# imsensor-v01.net
KiCad netlist of a schematic drawn in EAGLE
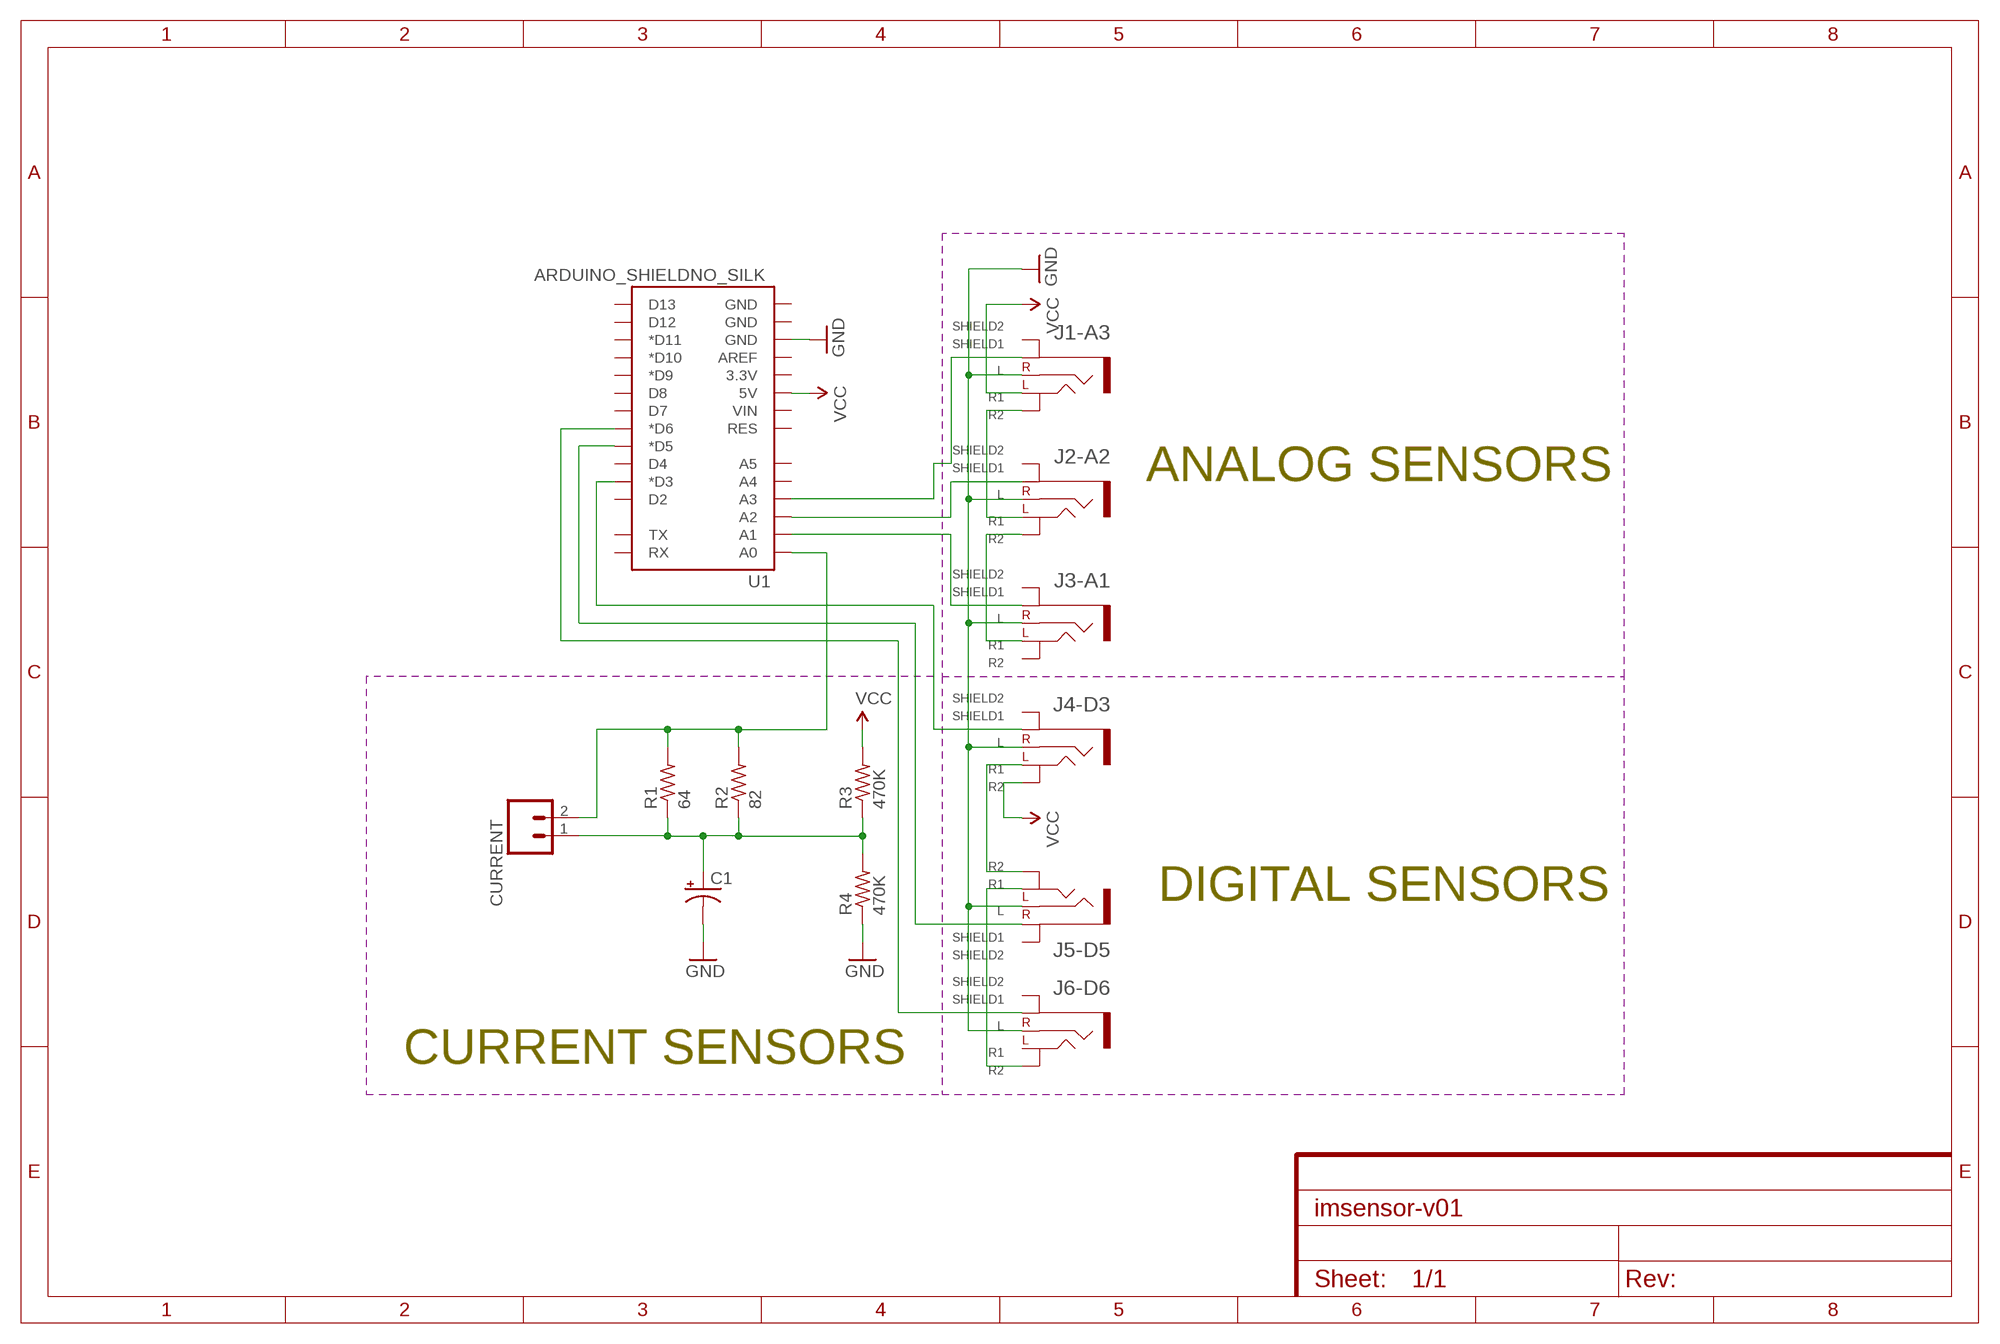
[diagram p0: schematic, sheet 1]

(export (version "E")
  (design (tool "Eeschema 10.0.6"))
  (components
    (comp (ref "C1")
      (value "10UF-25V-20%(PTH)")
      (footprint "eagle-import:CPOL-RADIAL-10UF-25V")
      (libsource (lib "eagle-import") (part "10UF-25V-20%(PTH)"))
    )
    (comp (ref "CURRENT")
      (value "M02PTH")
      (footprint "eagle-import:1X02")
      (libsource (lib "eagle-import") (part "M02PTH"))
    )
    (comp (ref "J1-A3")
      (value "PJ-313-SPAD")
      (footprint "eagle-import:PJ-313-5PIN-SMALL")
      (libsource (lib "eagle-import") (part "PJ-313-SPAD"))
    )
    (comp (ref "J2-A2")
      (value "PJ-313-SPAD")
      (footprint "eagle-import:PJ-313-5PIN-SMALL")
      (libsource (lib "eagle-import") (part "PJ-313-SPAD"))
    )
    (comp (ref "J3-A1")
      (value "PJ-313-SPAD")
      (footprint "eagle-import:PJ-313-5PIN-SMALL")
      (libsource (lib "eagle-import") (part "PJ-313-SPAD"))
    )
    (comp (ref "J4-D3")
      (value "PJ-313-SPAD")
      (footprint "eagle-import:PJ-313-5PIN-SMALL")
      (libsource (lib "eagle-import") (part "PJ-313-SPAD"))
    )
    (comp (ref "J5-D5")
      (value "PJ-313-SPAD")
      (footprint "eagle-import:PJ-313-5PIN-SMALL")
      (libsource (lib "eagle-import") (part "PJ-313-SPAD"))
    )
    (comp (ref "J6-D6")
      (value "PJ-313-SPAD")
      (footprint "eagle-import:PJ-313-5PIN-SMALL")
      (libsource (lib "eagle-import") (part "PJ-313-SPAD"))
    )
    (comp (ref "R1")
      (value "64")
      (footprint "eagle-import:0207_10")
      (libsource (lib "eagle-import") (part "R-US_0207/10"))
    )
    (comp (ref "R2")
      (value "82")
      (footprint "eagle-import:0207_10")
      (libsource (lib "eagle-import") (part "R-US_0207/10"))
    )
    (comp (ref "R3")
      (value "470K")
      (footprint "eagle-import:0207_10")
      (libsource (lib "eagle-import") (part "R-US_0207/10"))
    )
    (comp (ref "R4")
      (value "470K")
      (footprint "eagle-import:0207_10")
      (libsource (lib "eagle-import") (part "R-US_0207/10"))
    )
    (comp (ref "U1")
      (value "ARDUINO_SHIELDNO_SILK")
      (footprint "eagle-import:DUEMILANOVE_VIAS")
      (libsource (lib "eagle-import") (part "ARDUINO_SHIELDNO_SILK"))
    )
  )
  (nets
    (net (code "1") (name "GND") (class "Default")
      (node (ref "C1") (pin "2") (pinfunction "-_2") (pintype "passive"))
      (node (ref "J1-A3") (pin "2") (pinfunction "R_2") (pintype "bidirectional"))
      (node (ref "J2-A2") (pin "2") (pinfunction "R_2") (pintype "bidirectional"))
      (node (ref "J3-A1") (pin "2") (pinfunction "R_2") (pintype "bidirectional"))
      (node (ref "J4-D3") (pin "2") (pinfunction "R_2") (pintype "bidirectional"))
      (node (ref "J5-D5") (pin "2") (pinfunction "R_2") (pintype "bidirectional"))
      (node (ref "J6-D6") (pin "2") (pinfunction "R_2") (pintype "bidirectional"))
      (node (ref "R4") (pin "1") (pinfunction "1_1") (pintype "passive"))
      (node (ref "U1") (pin "GND@2") (pinfunction "GND_GND@2") (pintype "bidirectional"))
    )
    (net (code "2") (name "Net-(C1-+)") (class "Default")
      (node (ref "C1") (pin "1") (pinfunction "+_1") (pintype "passive"))
      (node (ref "CURRENT") (pin "1") (pinfunction "1_1") (pintype "passive"))
      (node (ref "R1") (pin "1") (pinfunction "1_1") (pintype "passive"))
      (node (ref "R2") (pin "1") (pinfunction "1_1") (pintype "passive"))
      (node (ref "R3") (pin "1") (pinfunction "1_1") (pintype "passive"))
      (node (ref "R4") (pin "2") (pinfunction "2_2") (pintype "passive"))
    )
    (net (code "3") (name "Net-(CURRENT-Pad2)") (class "Default")
      (node (ref "CURRENT") (pin "2") (pinfunction "2_2") (pintype "passive"))
      (node (ref "R1") (pin "2") (pinfunction "2_2") (pintype "passive"))
      (node (ref "R2") (pin "2") (pinfunction "2_2") (pintype "passive"))
      (node (ref "U1") (pin "A0") (pinfunction "A0_A0") (pintype "bidirectional"))
    )
    (net (code "4") (name "Net-(J1-A3-L2)") (class "Default")
      (node (ref "J1-A3") (pin "3.2") (pinfunction "L2_3.2") (pintype "bidirectional"))
      (node (ref "J2-A2") (pin "3.1") (pinfunction "L1_3.1") (pintype "bidirectional"))
    )
    (net (code "5") (name "Net-(J1-A3-SHIELD1)") (class "Default")
      (node (ref "J1-A3") (pin "1.1") (pinfunction "SHIELD1_1.1") (pintype "bidirectional"))
      (node (ref "U1") (pin "A3") (pinfunction "A3_A3") (pintype "bidirectional"))
    )
    (net (code "6") (name "Net-(J2-A2-L2)") (class "Default")
      (node (ref "J2-A2") (pin "3.2") (pinfunction "L2_3.2") (pintype "bidirectional"))
      (node (ref "J3-A1") (pin "3.1") (pinfunction "L1_3.1") (pintype "bidirectional"))
    )
    (net (code "7") (name "Net-(J2-A2-SHIELD1)") (class "Default")
      (node (ref "J2-A2") (pin "1.1") (pinfunction "SHIELD1_1.1") (pintype "bidirectional"))
      (node (ref "U1") (pin "A2") (pinfunction "A2_A2") (pintype "bidirectional"))
    )
    (net (code "8") (name "Net-(J3-A1-SHIELD1)") (class "Default")
      (node (ref "J3-A1") (pin "1.1") (pinfunction "SHIELD1_1.1") (pintype "bidirectional"))
      (node (ref "U1") (pin "A1") (pinfunction "A1_A1") (pintype "bidirectional"))
    )
    (net (code "9") (name "Net-(J4-D3-L1)") (class "Default")
      (node (ref "J4-D3") (pin "3.1") (pinfunction "L1_3.1") (pintype "bidirectional"))
      (node (ref "J5-D5") (pin "3.2") (pinfunction "L2_3.2") (pintype "bidirectional"))
    )
    (net (code "10") (name "Net-(J4-D3-SHIELD1)") (class "Default")
      (node (ref "J4-D3") (pin "1.1") (pinfunction "SHIELD1_1.1") (pintype "bidirectional"))
      (node (ref "U1") (pin "D3") (pinfunction "*D3_D3") (pintype "bidirectional"))
    )
    (net (code "11") (name "Net-(J5-D5-L1)") (class "Default")
      (node (ref "J5-D5") (pin "3.1") (pinfunction "L1_3.1") (pintype "bidirectional"))
      (node (ref "J6-D6") (pin "3.2") (pinfunction "L2_3.2") (pintype "bidirectional"))
    )
    (net (code "12") (name "Net-(J5-D5-SHIELD1)") (class "Default")
      (node (ref "J5-D5") (pin "1.1") (pinfunction "SHIELD1_1.1") (pintype "bidirectional"))
      (node (ref "U1") (pin "D5") (pinfunction "*D5_D5") (pintype "bidirectional"))
    )
    (net (code "13") (name "Net-(J6-D6-SHIELD1)") (class "Default")
      (node (ref "J6-D6") (pin "1.1") (pinfunction "SHIELD1_1.1") (pintype "bidirectional"))
      (node (ref "U1") (pin "D6") (pinfunction "*D6_D6") (pintype "bidirectional"))
    )
    (net (code "14") (name "VCC") (class "Default")
      (node (ref "J1-A3") (pin "3.1") (pinfunction "L1_3.1") (pintype "bidirectional"))
      (node (ref "J4-D3") (pin "3.2") (pinfunction "L2_3.2") (pintype "bidirectional"))
      (node (ref "R3") (pin "2") (pinfunction "2_2") (pintype "passive"))
      (node (ref "U1") (pin "5V") (pinfunction "5V_5V") (pintype "bidirectional"))
    )
    (net (code "15") (name "unconnected-(J1-A3-SHIELD2-Pad1.2)") (class "Default")
      (node (ref "J1-A3") (pin "1.2") (pinfunction "SHIELD2_1.2") (pintype "bidirectional"))
    )
    (net (code "16") (name "unconnected-(J2-A2-SHIELD2-Pad1.2)") (class "Default")
      (node (ref "J2-A2") (pin "1.2") (pinfunction "SHIELD2_1.2") (pintype "bidirectional"))
    )
    (net (code "17") (name "unconnected-(J3-A1-L2-Pad3.2)") (class "Default")
      (node (ref "J3-A1") (pin "3.2") (pinfunction "L2_3.2") (pintype "bidirectional"))
    )
    (net (code "18") (name "unconnected-(J3-A1-SHIELD2-Pad1.2)") (class "Default")
      (node (ref "J3-A1") (pin "1.2") (pinfunction "SHIELD2_1.2") (pintype "bidirectional"))
    )
    (net (code "19") (name "unconnected-(J4-D3-SHIELD2-Pad1.2)") (class "Default")
      (node (ref "J4-D3") (pin "1.2") (pinfunction "SHIELD2_1.2") (pintype "bidirectional"))
    )
    (net (code "20") (name "unconnected-(J5-D5-SHIELD2-Pad1.2)") (class "Default")
      (node (ref "J5-D5") (pin "1.2") (pinfunction "SHIELD2_1.2") (pintype "bidirectional"))
    )
    (net (code "21") (name "unconnected-(J6-D6-L1-Pad3.1)") (class "Default")
      (node (ref "J6-D6") (pin "3.1") (pinfunction "L1_3.1") (pintype "bidirectional"))
    )
    (net (code "22") (name "unconnected-(J6-D6-SHIELD2-Pad1.2)") (class "Default")
      (node (ref "J6-D6") (pin "1.2") (pinfunction "SHIELD2_1.2") (pintype "bidirectional"))
    )
    (net (code "23") (name "unconnected-(U1-*D9-PadD9)") (class "Default")
      (node (ref "U1") (pin "D9") (pinfunction "*D9_D9") (pintype "bidirectional"))
    )
    (net (code "24") (name "unconnected-(U1-*D10-PadD10)") (class "Default")
      (node (ref "U1") (pin "D10") (pinfunction "*D10_D10") (pintype "bidirectional"))
    )
    (net (code "25") (name "unconnected-(U1-*D11-PadD11)") (class "Default")
      (node (ref "U1") (pin "D11") (pinfunction "*D11_D11") (pintype "bidirectional"))
    )
    (net (code "26") (name "unconnected-(U1-GND-PadGND@0)") (class "Default")
      (node (ref "U1") (pin "GND@0") (pinfunction "GND_GND@0") (pintype "bidirectional"))
    )
    (net (code "27") (name "unconnected-(U1-GND-PadGND@1)") (class "Default")
      (node (ref "U1") (pin "GND@1") (pinfunction "GND_GND@1") (pintype "bidirectional"))
    )
    (net (code "28") (name "unconnected-(U1-Pad3.3V)") (class "Default")
      (node (ref "U1") (pin "3.3V") (pinfunction "3.3V_3.3V") (pintype "bidirectional"))
    )
    (net (code "29") (name "unconnected-(U1-PadA4)") (class "Default")
      (node (ref "U1") (pin "A4") (pinfunction "A4_A4") (pintype "bidirectional"))
    )
    (net (code "30") (name "unconnected-(U1-PadA5)") (class "Default")
      (node (ref "U1") (pin "A5") (pinfunction "A5_A5") (pintype "bidirectional"))
    )
    (net (code "31") (name "unconnected-(U1-PadAREF)") (class "Default")
      (node (ref "U1") (pin "AREF") (pinfunction "AREF_AREF") (pintype "bidirectional"))
    )
    (net (code "32") (name "unconnected-(U1-PadD2)") (class "Default")
      (node (ref "U1") (pin "D2") (pinfunction "D2_D2") (pintype "bidirectional"))
    )
    (net (code "33") (name "unconnected-(U1-PadD4)") (class "Default")
      (node (ref "U1") (pin "D4") (pinfunction "D4_D4") (pintype "bidirectional"))
    )
    (net (code "34") (name "unconnected-(U1-PadD7)") (class "Default")
      (node (ref "U1") (pin "D7") (pinfunction "D7_D7") (pintype "bidirectional"))
    )
    (net (code "35") (name "unconnected-(U1-PadD8)") (class "Default")
      (node (ref "U1") (pin "D8") (pinfunction "D8_D8") (pintype "bidirectional"))
    )
    (net (code "36") (name "unconnected-(U1-PadD12)") (class "Default")
      (node (ref "U1") (pin "D12") (pinfunction "D12_D12") (pintype "bidirectional"))
    )
    (net (code "37") (name "unconnected-(U1-PadD13)") (class "Default")
      (node (ref "U1") (pin "D13") (pinfunction "D13_D13") (pintype "bidirectional"))
    )
    (net (code "38") (name "unconnected-(U1-PadRES)") (class "Default")
      (node (ref "U1") (pin "RES") (pinfunction "RES_RES") (pintype "bidirectional"))
    )
    (net (code "39") (name "unconnected-(U1-PadRX)") (class "Default")
      (node (ref "U1") (pin "RX") (pinfunction "RX_RX") (pintype "bidirectional"))
    )
    (net (code "40") (name "unconnected-(U1-PadTX)") (class "Default")
      (node (ref "U1") (pin "TX") (pinfunction "TX_TX") (pintype "bidirectional"))
    )
    (net (code "41") (name "unconnected-(U1-PadVIN)") (class "Default")
      (node (ref "U1") (pin "VIN") (pinfunction "VIN_VIN") (pintype "bidirectional"))
    )
  )
)
